# Power.net
KiCad netlist of a schematic drawn in Altium Designer
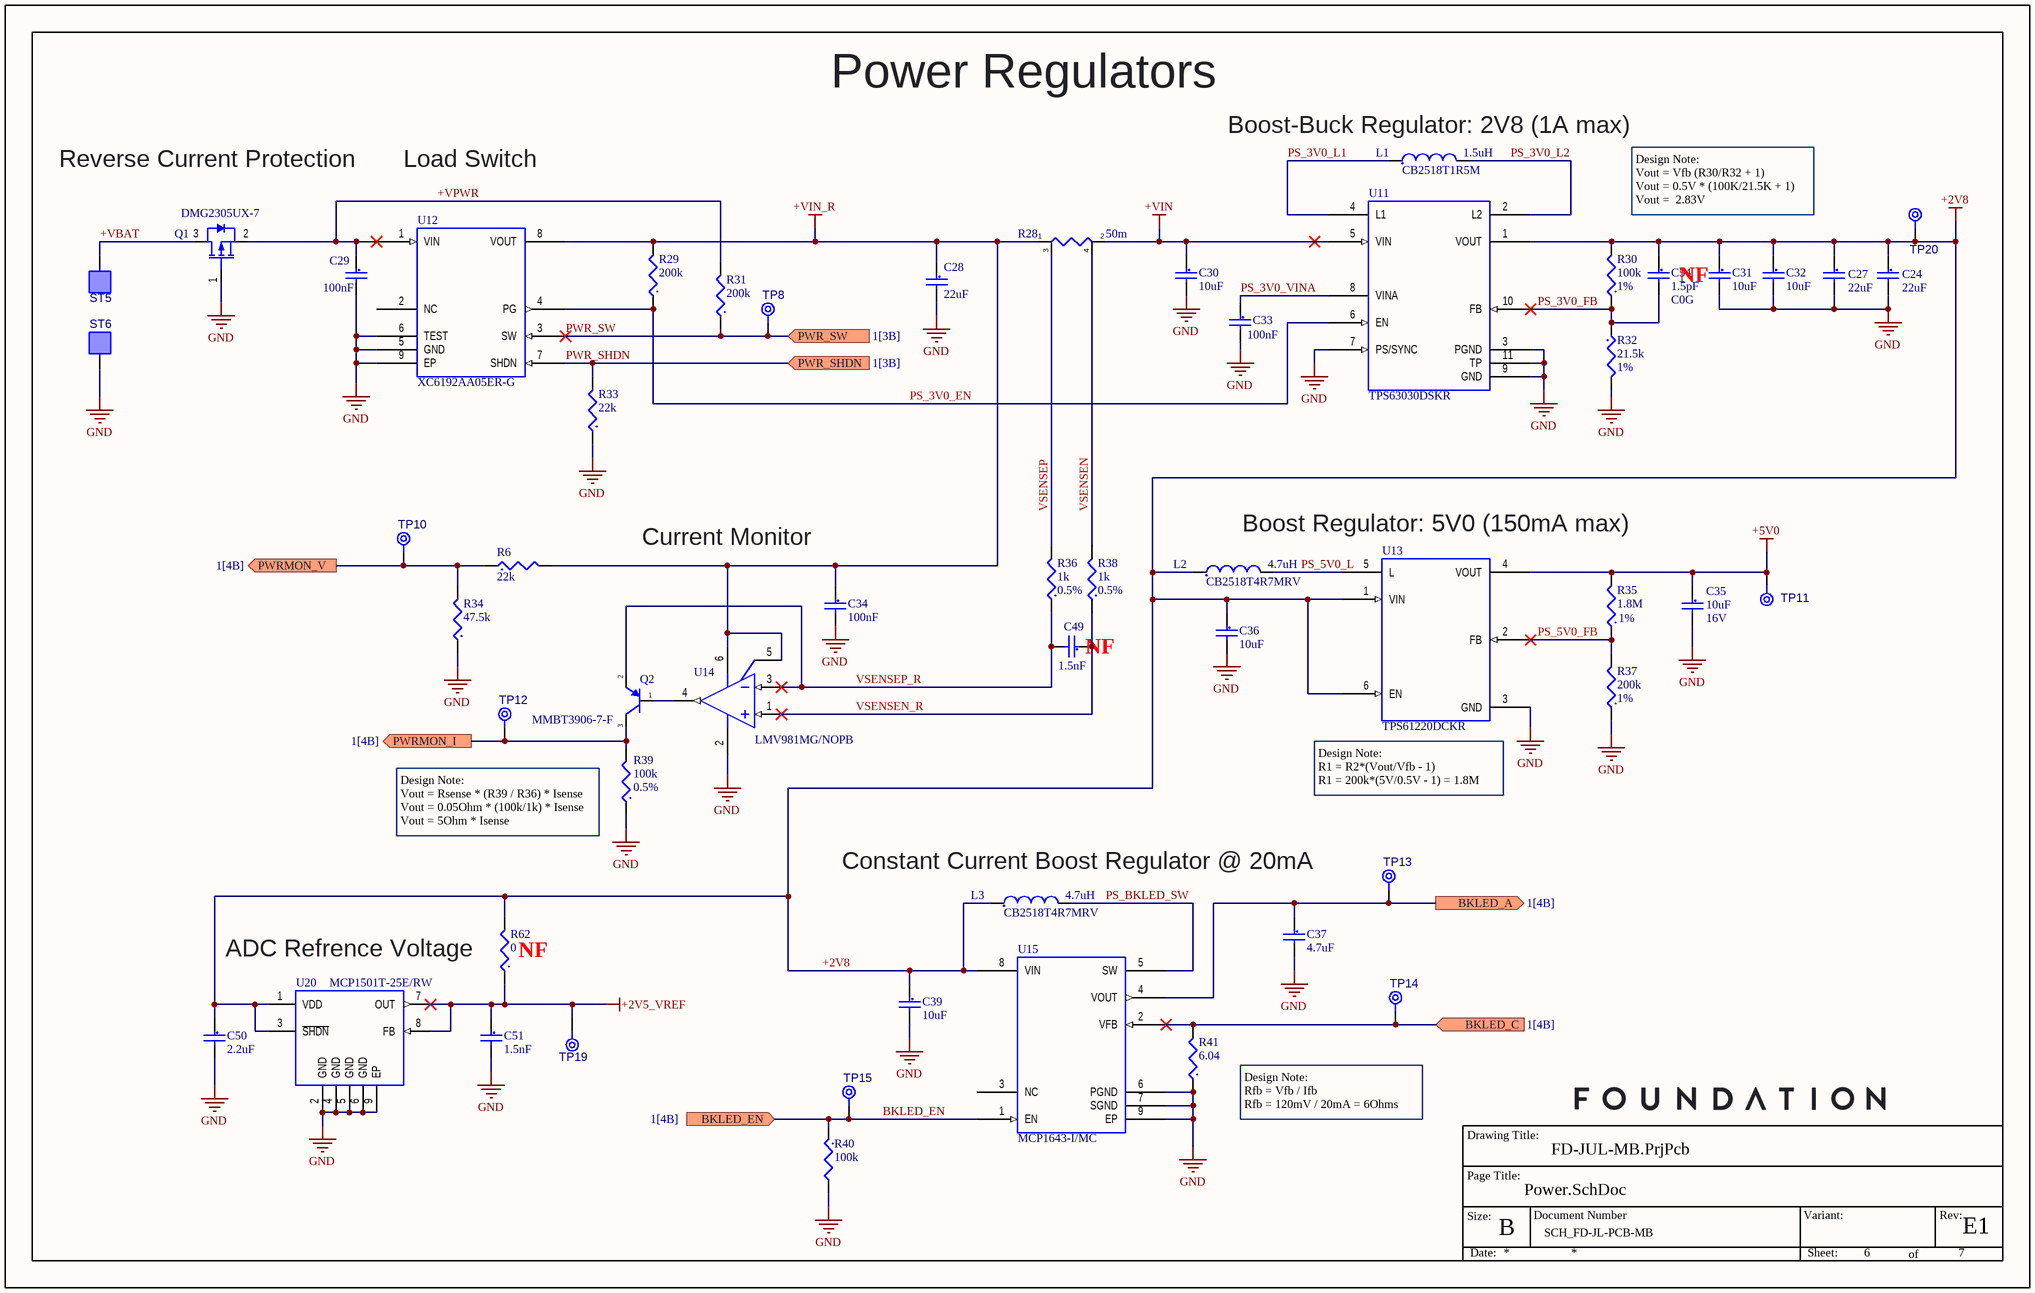
[diagram p0: Power.SchDoc]

(export (version "E")
  (design (tool "Eeschema 10.0.6"))
  (components
    (comp (ref "C24")
      (value "CAP CER 22uF 16V 10% X5R 0805")
      (footprint "CAPC0805(2012)145_L")
      (description "22µF ±10% 16V Ceramic Capacitor X5R 0805 (2012 Metric)")
      (fields
        (field (name "CAPACITANCE") "22uF")
        (field (name "TOLERANCE") "10%")
        (field (name "VOLTAGE") "16V")
      )
      (libsource (lib "Altium Concord Pro on A365") (part "CAP-NP-2"))
    )
    (comp (ref "C27")
      (value "CAP CER 22uF 16V 10% X5R 0805")
      (footprint "CAPC0805(2012)145_L")
      (description "22µF ±10% 16V Ceramic Capacitor X5R 0805 (2012 Metric)")
      (fields
        (field (name "CAPACITANCE") "22uF")
        (field (name "TOLERANCE") "10%")
        (field (name "VOLTAGE") "16V")
      )
      (libsource (lib "Altium Concord Pro on A365") (part "CAP-NP-2"))
    )
    (comp (ref "C28")
      (value "CAP CER 22uF 16V 10% X5R 0805")
      (footprint "CAPC0805(2012)145_L")
      (description "22µF ±10% 16V Ceramic Capacitor X5R 0805 (2012 Metric)")
      (fields
        (field (name "CAPACITANCE") "22uF")
        (field (name "TOLERANCE") "10%")
        (field (name "VOLTAGE") "16V")
      )
      (libsource (lib "Altium Concord Pro on A365") (part "CAP-NP-2"))
    )
    (comp (ref "C29")
      (value "CAP CER 0.1uF 16V 10% X7R 0402")
      (footprint "CAPC0402(1005)55_L")
      (description "0.1µF ±10% 16V Ceramic Capacitor X7R 0402 (1005 Metric)")
      (fields
        (field (name "CAPACITANCE") "100nF")
        (field (name "TOLERANCE") "10%")
        (field (name "VOLTAGE") "16V")
      )
      (libsource (lib "Altium Concord Pro on A365") (part "CAP-NP-2"))
    )
    (comp (ref "C30")
      (value "CAP CER 10uF 6.3V 20% X5R 0603")
      (footprint "CAPC0603(1608)90_L")
      (description "10µF ±20% 6.3V Ceramic Capacitor X5R 0603 (1608 Metric)")
      (fields
        (field (name "CAPACITANCE") "10uF")
        (field (name "TOLERANCE") "20%")
        (field (name "VOLTAGE") "6.3V")
      )
      (libsource (lib "Altium Concord Pro on A365") (part "CAP-NP-2"))
    )
    (comp (ref "C31")
      (value "CAP CER 10uF 6.3V 20% X5R 0603")
      (footprint "CAPC0603(1608)90_L")
      (description "10µF ±20% 6.3V Ceramic Capacitor X5R 0603 (1608 Metric)")
      (fields
        (field (name "CAPACITANCE") "10uF")
        (field (name "TOLERANCE") "20%")
        (field (name "VOLTAGE") "6.3V")
      )
      (libsource (lib "Altium Concord Pro on A365") (part "CAP-NP-2"))
    )
    (comp (ref "C32")
      (value "CAP CER 10uF 6.3V 20% X5R 0603")
      (footprint "CAPC0603(1608)90_L")
      (description "10µF ±20% 6.3V Ceramic Capacitor X5R 0603 (1608 Metric)")
      (fields
        (field (name "CAPACITANCE") "10uF")
        (field (name "TOLERANCE") "20%")
        (field (name "VOLTAGE") "6.3V")
      )
      (libsource (lib "Altium Concord Pro on A365") (part "CAP-NP-2"))
    )
    (comp (ref "C33")
      (value "CAP CER 0.1uF 16V 10% X7R 0402")
      (footprint "CAPC0402(1005)55_L")
      (description "0.1µF ±10% 16V Ceramic Capacitor X7R 0402 (1005 Metric)")
      (fields
        (field (name "CAPACITANCE") "100nF")
        (field (name "TOLERANCE") "10%")
        (field (name "VOLTAGE") "16V")
      )
      (libsource (lib "Altium Concord Pro on A365") (part "CAP-NP-2"))
    )
    (comp (ref "C34")
      (value "CAP CER 0.1uF 16V 10% X7R 0402")
      (footprint "CAPC0402(1005)55_L")
      (description "0.1µF ±10% 16V Ceramic Capacitor X7R 0402 (1005 Metric)")
      (fields
        (field (name "CAPACITANCE") "100nF")
        (field (name "TOLERANCE") "10%")
        (field (name "VOLTAGE") "16V")
      )
      (libsource (lib "Altium Concord Pro on A365") (part "CAP-NP-2"))
    )
    (comp (ref "C35")
      (value "CAP CER 10uF 16V 20% X5R 0603")
      (footprint "CAPC0603(1608)90_L")
      (description "10µF ±20% 16V Ceramic Capacitor X5R 0603 (1608 Metric)")
      (fields
        (field (name "CAPACITANCE") "10uF")
        (field (name "VOLTAGE RATING (DC)") "16V")
        (field (name "TOLERANCE") "20%")
      )
      (libsource (lib "Altium Concord Pro on A365") (part "CAP-NP-2"))
    )
    (comp (ref "C36")
      (value "CAP CER 10uF 6.3V 20% X5R 0603")
      (footprint "CAPC0603(1608)90_L")
      (description "10µF ±20% 6.3V Ceramic Capacitor X5R 0603 (1608 Metric)")
      (fields
        (field (name "CAPACITANCE") "10uF")
        (field (name "TOLERANCE") "20%")
        (field (name "VOLTAGE") "6.3V")
      )
      (libsource (lib "Altium Concord Pro on A365") (part "CAP-NP-2"))
    )
    (comp (ref "C37")
      (value "CAP CER 4.7uF 16V 10% X5R 0603")
      (footprint "CAPC0603(1608)90_L")
      (description "4.7µF ±10% 16V Ceramic Capacitor X5R 0603 (1608 Metric)")
      (fields (field (name "CAPACITANCE") "4.7uF") (field (name "TOLERANCE") "10%"))
      (libsource (lib "Altium Concord Pro on A365") (part "CAP-NP-2"))
    )
    (comp (ref "C39")
      (value "CAP CER 10uF 6.3V 20% X5R 0603")
      (footprint "CAPC0603(1608)90_L")
      (description "10µF ±20% 6.3V Ceramic Capacitor X5R 0603 (1608 Metric)")
      (fields
        (field (name "CAPACITANCE") "10uF")
        (field (name "TOLERANCE") "20%")
        (field (name "VOLTAGE") "6.3V")
      )
      (libsource (lib "Altium Concord Pro on A365") (part "CAP-NP-2"))
    )
    (comp (ref "C49")
      (value "CAP CER 1500pF 50V 10% X7R 0402")
      (footprint "CAPC0402(1005)55_L")
      (description "1500pF ±10% 50V Ceramic Capacitor X7R 0402 (1005 Metric)")
      (fields
        (field (name "CAPACITANCE") "1.5nF")
        (field (name "TOLERANCE") "10%")
        (field (name "VOLTAGE") "50V")
      )
      (libsource (lib "Altium Concord Pro on A365") (part "CAP-NP-2"))
    )
    (comp (ref "C50")
      (value "CAP CER 2.2uF 6.3V 10% X5R 0402")
      (footprint "CAPC0402(1005)55_L")
      (description "2.2µF ±10% 6.3V Ceramic Capacitor X5R 0402 (1005 Metric)")
      (fields (field (name "CAPACITANCE") "2.2uF") (field (name "TOLERANCE") "10%"))
      (libsource (lib "Altium Concord Pro on A365") (part "CAP-NP-2"))
    )
    (comp (ref "C51")
      (value "CAP CER 1500pF 50V 10% X7R 0402")
      (footprint "CAPC0402(1005)55_L")
      (description "1500pF ±10% 50V Ceramic Capacitor X7R 0402 (1005 Metric)")
      (fields
        (field (name "CAPACITANCE") "1.5nF")
        (field (name "VOLTAGE") "50V")
        (field (name "TOLERANCE") "10%")
      )
      (libsource (lib "Altium Concord Pro on A365") (part "CAP-NP-2"))
    )
    (comp (ref "C54")
      (value "CAP CER 1.5pF 50V C0G 0402")
      (footprint "CAPC0402(1005)55_L")
      (description "1.5pF ±0.25pF 50V Ceramic Capacitor C0G, NP0 0402 (1005 Metric)")
      (fields
        (field (name "CAPACITANCE") "1.5pF")
        (field (name "DIELECTRIC") "C0G")
        (field (name "TOLERANCE") "20%")
        (field (name "VOLTAGE") "50V")
      )
      (libsource (lib "Altium Concord Pro on A365") (part "CAP-NP-2"))
    )
    (comp (ref "L1")
      (value "CB2518T1R5M")
      (footprint "INDC1007(2518)_L")
      (description "1.5µH Unshielded Wirewound Inductor 1.4A 91mOhm Max 1007 (2518 Metric)")
      (fields (field (name "INDUCTANCE") "1.5uH") (field (name "TOLERANCE") "20%"))
      (libsource (lib "Altium Concord Pro on A365") (part "IND-NP-2"))
    )
    (comp (ref "L2")
      (value "CB2518T4R7MRV")
      (footprint "INDC1007(2518)_L")
      (description "4.7µH Unshielded Wirewound Inductor 820mA 130mOhm Max 1007 (2518 Metric)")
      (fields (field (name "INDUCTANCE") "4.7uH") (field (name "TOLERANCE") "20%"))
      (libsource (lib "Altium Concord Pro on A365") (part "IND-NP-2"))
    )
    (comp (ref "L3")
      (value "CB2518T4R7MRV")
      (footprint "INDC1007(2518)_L")
      (description "4.7µH Unshielded Wirewound Inductor 820mA 130mOhm Max 1007 (2518 Metric)")
      (fields (field (name "INDUCTANCE") "4.7uH") (field (name "TOLERANCE") "20%"))
      (libsource (lib "Altium Concord Pro on A365") (part "IND-NP-2"))
    )
    (comp (ref "Q1")
      (value "DMG2305UX-7")
      (footprint "DIOD-SOT23-3_A_V")
      (description "P-Channel 20V 4.2A (Ta) 1.4W (Ta) Surface Mount SOT-23")
      (libsource (lib "Altium Concord Pro on A365") (part "PMOS-GSD-3"))
    )
    (comp (ref "Q2")
      (value "MMBT3906-7-F")
      (footprint "DIOD-SOT23-3_A_V")
      (description "TRANS PNP 40V 0.2A SOT23-3")
      (libsource (lib "Altium Concord Pro on A365") (part "BJT-PNP-BEC-3"))
    )
    (comp (ref "R6")
      (value "RES 22K 1/16W 1% 0402")
      (footprint "RESC0402(1005)_L")
      (description "22 kOhms ±1% 0.063W, 1/16W Chip Resistor 0402 (1005 Metric)")
      (fields (field (name "RESISTANCE") "22k") (field (name "TOLERANCE") "1%"))
      (libsource (lib "Altium Concord Pro on A365") (part "RES-2"))
    )
    (comp (ref "R28")
      (value "RES4T 0.05 OHM 0.5% 1/2W 1206")
      (footprint "RESC4T1206(3216)_V")
      (description "50 mOhms ±0.5% 0.5W, 1/2W Chip Resistor 1206 (3216 Metric) Current Sense")
      (fields (field (name "RESISTANCE") "50m") (field (name "TOLERANCE") "1%"))
      (libsource (lib "Altium Concord Pro on A365") (part "RES-4-13-24"))
    )
    (comp (ref "R29")
      (value "RES 200K 1/16W 1% 0402")
      (footprint "RESC0402(1005)_L")
      (description "200 kOhms ±1% 0.063W, 1/16W Chip Resistor 0402 (1005 Metric) Moisture Resistant Thick Film")
      (fields (field (name "RESISTANCE") "200k") (field (name "TOLERANCE") "1%"))
      (libsource (lib "Altium Concord Pro on A365") (part "RES-2"))
    )
    (comp (ref "R30")
      (value "RES 100K 1/16W 1% 0402")
      (footprint "RESC0402(1005)_L")
      (description "100 kOhms ±1% 0.063W, 1/16W Chip Resistor 0402 (1005 Metric) Automotive AEC-Q200 Thick Film")
      (fields (field (name "RESISTANCE") "100k") (field (name "TOLERANCE") "1%"))
      (libsource (lib "Altium Concord Pro on A365") (part "RES-2"))
    )
    (comp (ref "R31")
      (value "RES 200K 1/16W 1% 0402")
      (footprint "RESC0402(1005)_L")
      (description "200 kOhms ±1% 0.063W, 1/16W Chip Resistor 0402 (1005 Metric) Moisture Resistant Thick Film")
      (fields (field (name "RESISTANCE") "200k") (field (name "TOLERANCE") "1%"))
      (libsource (lib "Altium Concord Pro on A365") (part "RES-2"))
    )
    (comp (ref "R32")
      (value "RES 21.5K 1/16W 1% 0402")
      (footprint "RESC0402(1005)_L")
      (description "21.5 kOhms ±1% 0.063W, 1/16W Chip Resistor 0402 (1005 Metric)")
      (fields (field (name "RESISTANCE") "21.5k") (field (name "TOLERANCE") "1%"))
      (libsource (lib "Altium Concord Pro on A365") (part "RES-2"))
    )
    (comp (ref "R33")
      (value "RES 22K 1/16W 1% 0402")
      (footprint "RESC0402(1005)_L")
      (description "22 kOhms ±1% 0.063W, 1/16W Chip Resistor 0402 (1005 Metric)")
      (fields (field (name "RESISTANCE") "22k") (field (name "TOLERANCE") "1%"))
      (libsource (lib "Altium Concord Pro on A365") (part "RES-2"))
    )
    (comp (ref "R34")
      (value "RES 47.5K 1/16W 1% 0402")
      (footprint "RESC0402(1005)_L")
      (description "47.5 kOhms ±1% 0.063W, 1/16W Chip Resistor 0402 (1005 Metric)")
      (fields (field (name "RESISTANCE") "47.5k") (field (name "TOLERANCE") "1%"))
      (libsource (lib "Altium Concord Pro on A365") (part "RES-2"))
    )
    (comp (ref "R35")
      (value "RES 1.8M 1/16W 1% 0402")
      (footprint "RESC0402(1005)_L")
      (description "1.8 MOhms ±1% 0.063W, 1/16W Chip Resistor 0402 (1005 Metric)")
      (fields (field (name "RESISTANCE") "1.8M") (field (name "TOLERANCE") "1%"))
      (libsource (lib "Altium Concord Pro on A365") (part "RES-2"))
    )
    (comp (ref "R36")
      (value "RES 1.0K 1/16W 1% 0402")
      (footprint "RESC0402(1005)_L")
      (description "1 kOhms ±0.5% 0.063W, 1/16W Chip Resistor 0402 (1005 Metric) Automotive AEC-Q200 Thin Film")
      (fields (field (name "RESISTANCE") "1k") (field (name "TOLERANCE") "0.5%"))
      (libsource (lib "Altium Concord Pro on A365") (part "RES-2"))
    )
    (comp (ref "R37")
      (value "RES 200K 1/16W 1% 0402")
      (footprint "RESC0402(1005)_L")
      (description "200 kOhms ±1% 0.063W, 1/16W Chip Resistor 0402 (1005 Metric) Moisture Resistant Thick Film")
      (fields (field (name "RESISTANCE") "200k") (field (name "TOLERANCE") "1%"))
      (libsource (lib "Altium Concord Pro on A365") (part "RES-2"))
    )
    (comp (ref "R38")
      (value "RES 1.0K 1/16W 1% 0402")
      (footprint "RESC0402(1005)_L")
      (description "1 kOhms ±0.5% 0.063W, 1/16W Chip Resistor 0402 (1005 Metric) Automotive AEC-Q200 Thin Film")
      (fields (field (name "RESISTANCE") "1k") (field (name "TOLERANCE") "0.5%"))
      (libsource (lib "Altium Concord Pro on A365") (part "RES-2"))
    )
    (comp (ref "R39")
      (value "RES 100K 1/16W 0.5% 0402")
      (footprint "RESC0402(1005)_L")
      (description "100 kOhms ±0.5% 0.063W, 1/16W Chip Resistor 0402 (1005 Metric)")
      (fields (field (name "RESISTANCE") "100k") (field (name "TOLERANCE") "0.5%"))
      (libsource (lib "Altium Concord Pro on A365") (part "RES-2"))
    )
    (comp (ref "R40")
      (value "RES 100K 1/16W 1% 0402")
      (footprint "RESC0402(1005)_L")
      (description "100 kOhms ±1% 0.063W, 1/16W Chip Resistor 0402 (1005 Metric) Automotive AEC-Q200 Thick Film")
      (fields (field (name "RESISTANCE") "100k") (field (name "TOLERANCE") "1%"))
      (libsource (lib "Altium Concord Pro on A365") (part "RES-2"))
    )
    (comp (ref "R41")
      (value "RES 6.04 OHM 1/16W 1% 0402")
      (footprint "RESC0402(1005)_L")
      (description "6.04 Ohms ±1% 0.063W, 1/16W Chip Resistor 0402 (1005 Metric)")
      (fields (field (name "RESISTANCE") "6.04") (field (name "TOLERANCE") "1%"))
      (libsource (lib "Altium Concord Pro on A365") (part "RES-2"))
    )
    (comp (ref "R62")
      (value "RES 0 OHM JUMPER 1/16W 0402")
      (footprint "RESC0402(1005)_L")
      (description "0 Ohms Jumper 0.063W, 1/16W Chip Resistor 0402 (1005 Metric)")
      (fields (field (name "RESISTANCE") "0") (field (name "TOLERANCE") "5%"))
      (libsource (lib "Altium Concord Pro on A365") (part "RES-2"))
    )
    (comp (ref "ST5")
      (value "PAD-2_54X2_54Y")
      (footprint "PAD-2_54X2_54Y")
      (description "Pad, 2.54mm x 2.54mm")
      (libsource (lib "Altium Concord Pro on A365") (part "PADR-1"))
    )
    (comp (ref "ST6")
      (value "PAD-2_54X2_54Y")
      (footprint "PAD-2_54X2_54Y")
      (description "Pad, 2.54mm x 2.54mm")
      (libsource (lib "") (part "PADR-1_1"))
    )
    (comp (ref "TP8")
      (value "TPAD8R")
      (footprint "TP08R")
      (description "0.8mm round")
      (libsource (lib "Altium Concord Pro on A365") (part "TP-R-1"))
    )
    (comp (ref "TP10")
      (value "TPAD8R")
      (footprint "TP08R")
      (description "0.8mm round")
      (libsource (lib "Altium Concord Pro on A365") (part "TP-R-1"))
    )
    (comp (ref "TP11")
      (value "TPAD8R")
      (footprint "TP08R")
      (description "0.8mm round")
      (libsource (lib "Altium Concord Pro on A365") (part "TP-R-1"))
    )
    (comp (ref "TP12")
      (value "TPAD8R")
      (footprint "TP08R")
      (description "0.8mm round")
      (libsource (lib "Altium Concord Pro on A365") (part "TP-R-1"))
    )
    (comp (ref "TP13")
      (value "TPAD8R")
      (footprint "TP08R")
      (description "0.8mm round")
      (libsource (lib "Altium Concord Pro on A365") (part "TP-R-1"))
    )
    (comp (ref "TP14")
      (value "TPAD8R")
      (footprint "TP08R")
      (description "0.8mm round")
      (libsource (lib "Altium Concord Pro on A365") (part "TP-R-1"))
    )
    (comp (ref "TP15")
      (value "TPAD8R")
      (footprint "TP08R")
      (description "0.8mm round")
      (libsource (lib "Altium Concord Pro on A365") (part "TP-R-1"))
    )
    (comp (ref "TP19")
      (value "TPAD8R")
      (footprint "TP08R")
      (description "0.8mm round")
      (libsource (lib "Altium Concord Pro on A365") (part "TP-R-1"))
    )
    (comp (ref "TP20")
      (value "TPAD8R")
      (footprint "TP08R")
      (description "0.8mm round")
      (libsource (lib "Altium Concord Pro on A365") (part "TP-R-1"))
    )
    (comp (ref "U11")
      (value "TPS63030DSKR")
      (footprint "TI - VSON-10_L")
      (libsource (lib "Altium Concord Pro on A365") (part "TPS6303"))
    )
    (comp (ref "U12")
      (value "XC6192AA05ER-G")
      (footprint "TORX - USP-8B06_V")
      (description "Power Switch/Driver 1:1 P-Channel 400mA USP-8B06")
      (libsource (lib "Altium Concord Pro on A365") (part "XC6192-G"))
    )
    (comp (ref "U13")
      (value "TPS61220DCKR")
      (footprint "TI - SC70-6_L")
      (libsource (lib "Altium Concord Pro on A365") (part "TPS6122"))
    )
    (comp (ref "U14")
      (value "LMV981MG/NOPB")
      (footprint "TI - SC70-6_L")
      (description "General Purpose Amplifier 1 Circuit Rail-to-Rail SC-70-6")
      (libsource (lib "Altium Concord Pro on A365") (part "AMP-OPA-LMV981-6"))
    )
    (comp (ref "U15")
      (value "MCP1643-I/MC")
      (footprint "MCHP - DFN-8_L")
      (description "LED Driver IC 1 Output DC DC Regulator Step-Up (Boost) PWM Dimming 550mA 8-DFN (2x3)")
      (libsource (lib "Altium Concord Pro on A365") (part "MCP1643-I/MC"))
    )
    (comp (ref "U20")
      (value "MCP1501T-25E/RW")
      (footprint "MCHP - WDFN-8_L")
      (description "Series Voltage Reference IC 2.5V ±0.1%  8-WDFN (2x2)")
      (libsource (lib "Altium Concord Pro on A365") (part "MCP1501-xx/RW"))
    )
  )
  (nets
    (net (code "1") (name "+2V5_VREF") (class "Default")
      (node (ref "C51") (pin "1") (pinfunction "1_1") (pintype "passive"))
      (node (ref "R62") (pin "1") (pinfunction "1_1") (pintype "passive"))
      (node (ref "TP19") (pin "1") (pinfunction "TP_1") (pintype "passive"))
      (node (ref "U20") (pin "7") (pinfunction "OUT_7") (pintype "output"))
      (node (ref "U20") (pin "8") (pinfunction "FB_8") (pintype "input"))
    )
    (net (code "2") (name "+2V8") (class "Default")
      (node (ref "C24") (pin "1") (pinfunction "1_1") (pintype "passive"))
      (node (ref "C27") (pin "1") (pinfunction "1_1") (pintype "passive"))
      (node (ref "C31") (pin "1") (pinfunction "1_1") (pintype "passive"))
      (node (ref "C32") (pin "1") (pinfunction "1_1") (pintype "passive"))
      (node (ref "C36") (pin "1") (pinfunction "1_1") (pintype "passive"))
      (node (ref "C39") (pin "1") (pinfunction "1_1") (pintype "passive"))
      (node (ref "C50") (pin "1") (pinfunction "1_1") (pintype "passive"))
      (node (ref "C54") (pin "1") (pinfunction "1_1") (pintype "passive"))
      (node (ref "L2") (pin "1") (pinfunction "1_1") (pintype "passive"))
      (node (ref "L3") (pin "1") (pinfunction "1_1") (pintype "passive"))
      (node (ref "R30") (pin "2") (pinfunction "2_2") (pintype "passive"))
      (node (ref "R62") (pin "2") (pinfunction "2_2") (pintype "passive"))
      (node (ref "TP20") (pin "1") (pinfunction "TP_1") (pintype "passive"))
      (node (ref "U11") (pin "1") (pinfunction "VOUT_1") (pintype "passive"))
      (node (ref "U13") (pin "1") (pinfunction "VIN_1") (pintype "input"))
      (node (ref "U13") (pin "6") (pinfunction "EN_6") (pintype "input"))
      (node (ref "U15") (pin "8") (pinfunction "VIN_8") (pintype "power_in"))
      (node (ref "U20") (pin "1") (pinfunction "VDD_1") (pintype "power_in"))
      (node (ref "U20") (pin "3") (pinfunction "~{SHDN}_3") (pintype "passive"))
    )
    (net (code "3") (name "+5V0") (class "Default")
      (node (ref "C35") (pin "1") (pinfunction "1_1") (pintype "passive"))
      (node (ref "R35") (pin "2") (pinfunction "2_2") (pintype "passive"))
      (node (ref "TP11") (pin "1") (pinfunction "TP_1") (pintype "passive"))
      (node (ref "U13") (pin "4") (pinfunction "VOUT_4") (pintype "power_in"))
    )
    (net (code "4") (name "+VIN") (class "Default")
      (node (ref "C30") (pin "1") (pinfunction "1_1") (pintype "passive"))
      (node (ref "R28") (pin "2") (pinfunction "I2_2") (pintype "passive"))
      (node (ref "U11") (pin "5") (pinfunction "VIN_5") (pintype "input"))
    )
    (net (code "5") (name "+VIN_R") (class "Default")
      (node (ref "C28") (pin "1") (pinfunction "1_1") (pintype "passive"))
      (node (ref "C34") (pin "1") (pinfunction "1_1") (pintype "passive"))
      (node (ref "R28") (pin "1") (pinfunction "I1_1") (pintype "passive"))
      (node (ref "R29") (pin "2") (pinfunction "2_2") (pintype "passive"))
      (node (ref "R6") (pin "2") (pinfunction "2_2") (pintype "passive"))
      (node (ref "U12") (pin "8") (pinfunction "VOUT_8") (pintype "power_in"))
      (node (ref "U14") (pin "5") (pinfunction "~{SHDN}_5") (pintype "passive"))
      (node (ref "U14") (pin "6") (pinfunction "VDD_6") (pintype "power_in"))
    )
    (net (code "6") (name "/+VBAT") (class "Default")
      (node (ref "Q1") (pin "3") (pinfunction "DRAIN_3") (pintype "passive"))
      (node (ref "ST5") (pin "1") (pinfunction "1_1") (pintype "passive"))
    )
    (net (code "7") (name "/+VPWR") (class "Default")
      (node (ref "C29") (pin "1") (pinfunction "1_1") (pintype "passive"))
      (node (ref "Q1") (pin "2") (pinfunction "SOURCE_2") (pintype "passive"))
      (node (ref "R31") (pin "2") (pinfunction "2_2") (pintype "passive"))
      (node (ref "U12") (pin "1") (pinfunction "VIN_1") (pintype "input"))
    )
    (net (code "8") (name "/BKLED_A") (class "Default")
      (node (ref "C37") (pin "1") (pinfunction "1_1") (pintype "passive"))
      (node (ref "TP13") (pin "1") (pinfunction "TP_1") (pintype "passive"))
      (node (ref "U15") (pin "4") (pinfunction "VOUT_4") (pintype "output"))
    )
    (net (code "9") (name "/BKLED_C") (class "Default")
      (node (ref "R41") (pin "2") (pinfunction "2_2") (pintype "passive"))
      (node (ref "TP14") (pin "1") (pinfunction "TP_1") (pintype "passive"))
      (node (ref "U15") (pin "2") (pinfunction "VFB_2") (pintype "input"))
    )
    (net (code "10") (name "/BKLED_EN") (class "Default")
      (node (ref "R40") (pin "1") (pinfunction "1_1") (pintype "passive"))
      (node (ref "TP15") (pin "1") (pinfunction "TP_1") (pintype "passive"))
      (node (ref "U15") (pin "1") (pinfunction "EN_1") (pintype "input"))
    )
    (net (code "11") (name "/PS_3V0_EN") (class "Default")
      (node (ref "R29") (pin "1") (pinfunction "1_1") (pintype "passive"))
      (node (ref "U11") (pin "6") (pinfunction "EN_6") (pintype "input"))
      (node (ref "U12") (pin "4") (pinfunction "PG_4") (pintype "output"))
    )
    (net (code "12") (name "/PS_3V0_FB") (class "Default")
      (node (ref "C54") (pin "2") (pinfunction "2_2") (pintype "passive"))
      (node (ref "R30") (pin "1") (pinfunction "1_1") (pintype "passive"))
      (node (ref "R32") (pin "1") (pinfunction "1_1") (pintype "passive"))
      (node (ref "U11") (pin "10") (pinfunction "FB_10") (pintype "input"))
    )
    (net (code "13") (name "/PS_3V0_L1") (class "Default")
      (node (ref "L1") (pin "1") (pinfunction "1_1") (pintype "passive"))
      (node (ref "U11") (pin "4") (pinfunction "L1_4") (pintype "passive"))
    )
    (net (code "14") (name "/PS_3V0_L2") (class "Default")
      (node (ref "L1") (pin "2") (pinfunction "2_2") (pintype "passive"))
      (node (ref "U11") (pin "2") (pinfunction "L2_2") (pintype "passive"))
    )
    (net (code "15") (name "/PS_3V0_VINA") (class "Default")
      (node (ref "C33") (pin "1") (pinfunction "1_1") (pintype "passive"))
      (node (ref "U11") (pin "8") (pinfunction "VINA_8") (pintype "power_in"))
    )
    (net (code "16") (name "/PS_5V0_FB") (class "Default")
      (node (ref "R35") (pin "1") (pinfunction "1_1") (pintype "passive"))
      (node (ref "R37") (pin "2") (pinfunction "2_2") (pintype "passive"))
      (node (ref "U13") (pin "2") (pinfunction "FB_2") (pintype "input"))
    )
    (net (code "17") (name "/PS_5V0_L") (class "Default")
      (node (ref "L2") (pin "2") (pinfunction "2_2") (pintype "passive"))
      (node (ref "U13") (pin "5") (pinfunction "L_5") (pintype "passive"))
    )
    (net (code "18") (name "/PS_BKLED_SW") (class "Default")
      (node (ref "L3") (pin "2") (pinfunction "2_2") (pintype "passive"))
      (node (ref "U15") (pin "5") (pinfunction "SW_5") (pintype "passive"))
    )
    (net (code "19") (name "/PWRMON_I") (class "Default")
      (node (ref "Q2") (pin "3") (pinfunction "C_3") (pintype "passive"))
      (node (ref "R39") (pin "2") (pinfunction "2_2") (pintype "passive"))
      (node (ref "TP12") (pin "1") (pinfunction "TP_1") (pintype "passive"))
    )
    (net (code "20") (name "/PWRMON_V") (class "Default")
      (node (ref "R34") (pin "2") (pinfunction "2_2") (pintype "passive"))
      (node (ref "R6") (pin "1") (pinfunction "1_1") (pintype "passive"))
      (node (ref "TP10") (pin "1") (pinfunction "TP_1") (pintype "passive"))
    )
    (net (code "21") (name "/PWR_SHDN") (class "Default")
      (node (ref "R33") (pin "2") (pinfunction "2_2") (pintype "passive"))
      (node (ref "U12") (pin "7") (pinfunction "SHDN_7") (pintype "input"))
    )
    (net (code "22") (name "/PWR_SW") (class "Default")
      (node (ref "R31") (pin "1") (pinfunction "1_1") (pintype "passive"))
      (node (ref "TP8") (pin "1") (pinfunction "TP_1") (pintype "passive"))
      (node (ref "U12") (pin "3") (pinfunction "SW_3") (pintype "input"))
    )
    (net (code "23") (name "/VSENSEN") (class "Default")
      (node (ref "R28") (pin "4") (pinfunction "E2_4") (pintype "passive"))
      (node (ref "R38") (pin "2") (pinfunction "2_2") (pintype "passive"))
    )
    (net (code "24") (name "/VSENSEN_R") (class "Default")
      (node (ref "C49") (pin "1") (pinfunction "1_1") (pintype "passive"))
      (node (ref "R38") (pin "1") (pinfunction "1_1") (pintype "passive"))
      (node (ref "U14") (pin "1") (pinfunction "IN+_1") (pintype "input"))
    )
    (net (code "25") (name "/VSENSEP") (class "Default")
      (node (ref "R28") (pin "3") (pinfunction "E1_3") (pintype "passive"))
      (node (ref "R36") (pin "2") (pinfunction "2_2") (pintype "passive"))
    )
    (net (code "26") (name "/VSENSEP_R") (class "Default")
      (node (ref "C49") (pin "2") (pinfunction "2_2") (pintype "passive"))
      (node (ref "Q2") (pin "2") (pinfunction "E_2") (pintype "passive"))
      (node (ref "R36") (pin "1") (pinfunction "1_1") (pintype "passive"))
      (node (ref "U14") (pin "3") (pinfunction "IN-_3") (pintype "input"))
    )
    (net (code "27") (name "GND") (class "Default")
      (node (ref "C24") (pin "2") (pinfunction "2_2") (pintype "passive"))
      (node (ref "C27") (pin "2") (pinfunction "2_2") (pintype "passive"))
      (node (ref "C28") (pin "2") (pinfunction "2_2") (pintype "passive"))
      (node (ref "C29") (pin "2") (pinfunction "2_2") (pintype "passive"))
      (node (ref "C30") (pin "2") (pinfunction "2_2") (pintype "passive"))
      (node (ref "C31") (pin "2") (pinfunction "2_2") (pintype "passive"))
      (node (ref "C32") (pin "2") (pinfunction "2_2") (pintype "passive"))
      (node (ref "C33") (pin "2") (pinfunction "2_2") (pintype "passive"))
      (node (ref "C34") (pin "2") (pinfunction "2_2") (pintype "passive"))
      (node (ref "C35") (pin "2") (pinfunction "2_2") (pintype "passive"))
      (node (ref "C36") (pin "2") (pinfunction "2_2") (pintype "passive"))
      (node (ref "C37") (pin "2") (pinfunction "2_2") (pintype "passive"))
      (node (ref "C39") (pin "2") (pinfunction "2_2") (pintype "passive"))
      (node (ref "C50") (pin "2") (pinfunction "2_2") (pintype "passive"))
      (node (ref "C51") (pin "2") (pinfunction "2_2") (pintype "passive"))
      (node (ref "Q1") (pin "1") (pinfunction "GATE_1") (pintype "passive"))
      (node (ref "R32") (pin "2") (pinfunction "2_2") (pintype "passive"))
      (node (ref "R33") (pin "1") (pinfunction "1_1") (pintype "passive"))
      (node (ref "R34") (pin "1") (pinfunction "1_1") (pintype "passive"))
      (node (ref "R37") (pin "1") (pinfunction "1_1") (pintype "passive"))
      (node (ref "R39") (pin "1") (pinfunction "1_1") (pintype "passive"))
      (node (ref "R40") (pin "2") (pinfunction "2_2") (pintype "passive"))
      (node (ref "R41") (pin "1") (pinfunction "1_1") (pintype "passive"))
      (node (ref "ST6") (pin "1") (pinfunction "1_1") (pintype "passive"))
      (node (ref "U11") (pin "11") (pinfunction "TP_11") (pintype "passive"))
      (node (ref "U11") (pin "3") (pinfunction "PGND_3") (pintype "power_in"))
      (node (ref "U11") (pin "7") (pinfunction "PS/SYNC_7") (pintype "input"))
      (node (ref "U11") (pin "9") (pinfunction "GND_9") (pintype "power_in"))
      (node (ref "U12") (pin "5") (pinfunction "GND_5") (pintype "power_in"))
      (node (ref "U12") (pin "6") (pinfunction "TEST_6") (pintype "passive"))
      (node (ref "U12") (pin "9") (pinfunction "EP_9") (pintype "power_in"))
      (node (ref "U13") (pin "3") (pinfunction "GND_3") (pintype "power_in"))
      (node (ref "U14") (pin "2") (pinfunction "GND_2") (pintype "power_in"))
      (node (ref "U15") (pin "6") (pinfunction "PGND_6") (pintype "power_in"))
      (node (ref "U15") (pin "7") (pinfunction "SGND_7") (pintype "power_in"))
      (node (ref "U15") (pin "9") (pinfunction "EP_9") (pintype "power_in"))
      (node (ref "U20") (pin "2") (pinfunction "GND_2") (pintype "power_in"))
      (node (ref "U20") (pin "4") (pinfunction "GND_4") (pintype "power_in"))
      (node (ref "U20") (pin "5") (pinfunction "GND_5") (pintype "power_in"))
      (node (ref "U20") (pin "6") (pinfunction "GND_6") (pintype "power_in"))
      (node (ref "U20") (pin "9") (pinfunction "EP_9") (pintype "power_in"))
    )
    (net (code "28") (name "Net-(Q2-B)") (class "Default")
      (node (ref "Q2") (pin "1") (pinfunction "B_1") (pintype "passive"))
      (node (ref "U14") (pin "4") (pinfunction "OUT_4") (pintype "output"))
    )
    (net (code "29") (name "unconnected-(U12-NC-Pad2)") (class "Default")
      (node (ref "U12") (pin "2") (pinfunction "NC_2") (pintype "passive"))
    )
    (net (code "30") (name "unconnected-(U15-NC-Pad3)") (class "Default")
      (node (ref "U15") (pin "3") (pinfunction "NC_3") (pintype "passive"))
    )
  )
)
